# schemat-eagle.net
KiCad netlist of a schematic drawn in EAGLE
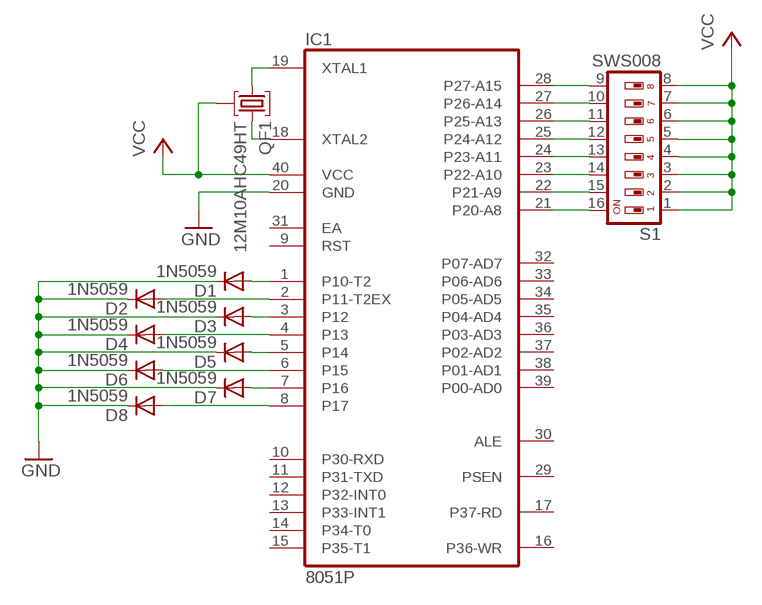
[diagram p0: schematic, sheet 1]

(export (version "E")
  (design (tool "Eeschema 10.0.6"))
  (components
    (comp (ref "D1")
      (value "1N5059")
      (footprint "eagle-import:DO204-10")
      (libsource (lib "eagle-import") (part "1N5059"))
    )
    (comp (ref "D2")
      (value "1N5059")
      (footprint "eagle-import:DO204-10")
      (libsource (lib "eagle-import") (part "1N5059"))
    )
    (comp (ref "D3")
      (value "1N5059")
      (footprint "eagle-import:DO204-10")
      (libsource (lib "eagle-import") (part "1N5059"))
    )
    (comp (ref "D4")
      (value "1N5059")
      (footprint "eagle-import:DO204-10")
      (libsource (lib "eagle-import") (part "1N5059"))
    )
    (comp (ref "D5")
      (value "1N5059")
      (footprint "eagle-import:DO204-10")
      (libsource (lib "eagle-import") (part "1N5059"))
    )
    (comp (ref "D6")
      (value "1N5059")
      (footprint "eagle-import:DO204-10")
      (libsource (lib "eagle-import") (part "1N5059"))
    )
    (comp (ref "D7")
      (value "1N5059")
      (footprint "eagle-import:DO204-10")
      (libsource (lib "eagle-import") (part "1N5059"))
    )
    (comp (ref "D8")
      (value "1N5059")
      (footprint "eagle-import:DO204-10")
      (libsource (lib "eagle-import") (part "1N5059"))
    )
    (comp (ref "IC1")
      (value "8051P")
      (footprint "eagle-import:DIL40")
      (libsource (lib "eagle-import") (part "8051P"))
    )
    (comp (ref "QF1")
      (value "12M10AHC49HT")
      (footprint "eagle-import:HC49U")
      (libsource (lib "eagle-import") (part "12M10AHC49HT"))
    )
    (comp (ref "S1")
      (value "SWS008")
      (footprint "eagle-import:SMS-008")
      (libsource (lib "eagle-import") (part "SWS008"))
    )
  )
  (nets
    (net (code "1") (name "GND") (class "Default")
      (node (ref "D1") (pin "C") (pinfunction "C_C") (pintype "passive"))
      (node (ref "D2") (pin "C") (pinfunction "C_C") (pintype "passive"))
      (node (ref "D3") (pin "C") (pinfunction "C_C") (pintype "passive"))
      (node (ref "D4") (pin "C") (pinfunction "C_C") (pintype "passive"))
      (node (ref "D5") (pin "C") (pinfunction "C_C") (pintype "passive"))
      (node (ref "D6") (pin "C") (pinfunction "C_C") (pintype "passive"))
      (node (ref "D7") (pin "C") (pinfunction "C_C") (pintype "passive"))
      (node (ref "D8") (pin "C") (pinfunction "C_C") (pintype "passive"))
      (node (ref "IC1") (pin "20") (pinfunction "GND_20") (pintype "power_in"))
    )
    (net (code "2") (name "Net-(IC1-P10-T2)") (class "Default")
      (node (ref "D1") (pin "A") (pinfunction "A_A") (pintype "passive"))
      (node (ref "IC1") (pin "1") (pinfunction "P10-T2_1") (pintype "bidirectional"))
    )
    (net (code "3") (name "Net-(IC1-P11-T2EX)") (class "Default")
      (node (ref "D2") (pin "A") (pinfunction "A_A") (pintype "passive"))
      (node (ref "IC1") (pin "2") (pinfunction "P11-T2EX_2") (pintype "bidirectional"))
    )
    (net (code "4") (name "Net-(IC1-P12)") (class "Default")
      (node (ref "D3") (pin "A") (pinfunction "A_A") (pintype "passive"))
      (node (ref "IC1") (pin "3") (pinfunction "P12_3") (pintype "bidirectional"))
    )
    (net (code "5") (name "Net-(IC1-P13)") (class "Default")
      (node (ref "D4") (pin "A") (pinfunction "A_A") (pintype "passive"))
      (node (ref "IC1") (pin "4") (pinfunction "P13_4") (pintype "bidirectional"))
    )
    (net (code "6") (name "Net-(IC1-P14)") (class "Default")
      (node (ref "D5") (pin "A") (pinfunction "A_A") (pintype "passive"))
      (node (ref "IC1") (pin "5") (pinfunction "P14_5") (pintype "bidirectional"))
    )
    (net (code "7") (name "Net-(IC1-P15)") (class "Default")
      (node (ref "D6") (pin "A") (pinfunction "A_A") (pintype "passive"))
      (node (ref "IC1") (pin "6") (pinfunction "P15_6") (pintype "bidirectional"))
    )
    (net (code "8") (name "Net-(IC1-P16)") (class "Default")
      (node (ref "D7") (pin "A") (pinfunction "A_A") (pintype "passive"))
      (node (ref "IC1") (pin "7") (pinfunction "P16_7") (pintype "bidirectional"))
    )
    (net (code "9") (name "Net-(IC1-P17)") (class "Default")
      (node (ref "D8") (pin "A") (pinfunction "A_A") (pintype "passive"))
      (node (ref "IC1") (pin "8") (pinfunction "P17_8") (pintype "bidirectional"))
    )
    (net (code "10") (name "Net-(IC1-P20-A8)") (class "Default")
      (node (ref "IC1") (pin "21") (pinfunction "P20-A8_21") (pintype "bidirectional"))
      (node (ref "S1") (pin "16") (pinfunction "16_16") (pintype "passive"))
    )
    (net (code "11") (name "Net-(IC1-P21-A9)") (class "Default")
      (node (ref "IC1") (pin "22") (pinfunction "P21-A9_22") (pintype "bidirectional"))
      (node (ref "S1") (pin "15") (pinfunction "15_15") (pintype "passive"))
    )
    (net (code "12") (name "Net-(IC1-P22-A10)") (class "Default")
      (node (ref "IC1") (pin "23") (pinfunction "P22-A10_23") (pintype "bidirectional"))
      (node (ref "S1") (pin "14") (pinfunction "14_14") (pintype "passive"))
    )
    (net (code "13") (name "Net-(IC1-P23-A11)") (class "Default")
      (node (ref "IC1") (pin "24") (pinfunction "P23-A11_24") (pintype "bidirectional"))
      (node (ref "S1") (pin "13") (pinfunction "13_13") (pintype "passive"))
    )
    (net (code "14") (name "Net-(IC1-P24-A12)") (class "Default")
      (node (ref "IC1") (pin "25") (pinfunction "P24-A12_25") (pintype "bidirectional"))
      (node (ref "S1") (pin "12") (pinfunction "12_12") (pintype "passive"))
    )
    (net (code "15") (name "Net-(IC1-P25-A13)") (class "Default")
      (node (ref "IC1") (pin "26") (pinfunction "P25-A13_26") (pintype "bidirectional"))
      (node (ref "S1") (pin "11") (pinfunction "11_11") (pintype "passive"))
    )
    (net (code "16") (name "Net-(IC1-P26-A14)") (class "Default")
      (node (ref "IC1") (pin "27") (pinfunction "P26-A14_27") (pintype "bidirectional"))
      (node (ref "S1") (pin "10") (pinfunction "10_10") (pintype "passive"))
    )
    (net (code "17") (name "Net-(IC1-P27-A15)") (class "Default")
      (node (ref "IC1") (pin "28") (pinfunction "P27-A15_28") (pintype "bidirectional"))
      (node (ref "S1") (pin "9") (pinfunction "9_9") (pintype "passive"))
    )
    (net (code "18") (name "Net-(IC1-XTAL1)") (class "Default")
      (node (ref "IC1") (pin "19") (pinfunction "XTAL1_19") (pintype "input"))
      (node (ref "QF1") (pin "1") (pinfunction "1_1") (pintype "passive"))
    )
    (net (code "19") (name "Net-(IC1-XTAL2)") (class "Default")
      (node (ref "IC1") (pin "18") (pinfunction "XTAL2_18") (pintype "input"))
      (node (ref "QF1") (pin "3") (pinfunction "3_3") (pintype "passive"))
    )
    (net (code "20") (name "VCC") (class "Default")
      (node (ref "IC1") (pin "40") (pinfunction "VCC_40") (pintype "power_in"))
      (node (ref "QF1") (pin "2") (pinfunction "2_2") (pintype "passive"))
      (node (ref "S1") (pin "1") (pinfunction "1_1") (pintype "passive"))
      (node (ref "S1") (pin "2") (pinfunction "2_2") (pintype "passive"))
      (node (ref "S1") (pin "3") (pinfunction "3_3") (pintype "passive"))
      (node (ref "S1") (pin "4") (pinfunction "4_4") (pintype "passive"))
      (node (ref "S1") (pin "5") (pinfunction "5_5") (pintype "passive"))
      (node (ref "S1") (pin "6") (pinfunction "6_6") (pintype "passive"))
      (node (ref "S1") (pin "7") (pinfunction "7_7") (pintype "passive"))
      (node (ref "S1") (pin "8") (pinfunction "8_8") (pintype "passive"))
    )
    (net (code "21") (name "unconnected-(IC1-ALE-Pad30)") (class "Default")
      (node (ref "IC1") (pin "30") (pinfunction "ALE_30") (pintype "output"))
    )
    (net (code "22") (name "unconnected-(IC1-EA-Pad31)") (class "Default")
      (node (ref "IC1") (pin "31") (pinfunction "EA_31") (pintype "input"))
    )
    (net (code "23") (name "unconnected-(IC1-P00-AD0-Pad39)") (class "Default")
      (node (ref "IC1") (pin "39") (pinfunction "P00-AD0_39") (pintype "bidirectional"))
    )
    (net (code "24") (name "unconnected-(IC1-P01-AD1-Pad38)") (class "Default")
      (node (ref "IC1") (pin "38") (pinfunction "P01-AD1_38") (pintype "bidirectional"))
    )
    (net (code "25") (name "unconnected-(IC1-P02-AD2-Pad37)") (class "Default")
      (node (ref "IC1") (pin "37") (pinfunction "P02-AD2_37") (pintype "bidirectional"))
    )
    (net (code "26") (name "unconnected-(IC1-P03-AD3-Pad36)") (class "Default")
      (node (ref "IC1") (pin "36") (pinfunction "P03-AD3_36") (pintype "bidirectional"))
    )
    (net (code "27") (name "unconnected-(IC1-P04-AD4-Pad35)") (class "Default")
      (node (ref "IC1") (pin "35") (pinfunction "P04-AD4_35") (pintype "bidirectional"))
    )
    (net (code "28") (name "unconnected-(IC1-P05-AD5-Pad34)") (class "Default")
      (node (ref "IC1") (pin "34") (pinfunction "P05-AD5_34") (pintype "bidirectional"))
    )
    (net (code "29") (name "unconnected-(IC1-P06-AD6-Pad33)") (class "Default")
      (node (ref "IC1") (pin "33") (pinfunction "P06-AD6_33") (pintype "bidirectional"))
    )
    (net (code "30") (name "unconnected-(IC1-P07-AD7-Pad32)") (class "Default")
      (node (ref "IC1") (pin "32") (pinfunction "P07-AD7_32") (pintype "bidirectional"))
    )
    (net (code "31") (name "unconnected-(IC1-P30-RXD-Pad10)") (class "Default")
      (node (ref "IC1") (pin "10") (pinfunction "P30-RXD_10") (pintype "bidirectional"))
    )
    (net (code "32") (name "unconnected-(IC1-P31-TXD-Pad11)") (class "Default")
      (node (ref "IC1") (pin "11") (pinfunction "P31-TXD_11") (pintype "bidirectional"))
    )
    (net (code "33") (name "unconnected-(IC1-P32-INT0-Pad12)") (class "Default")
      (node (ref "IC1") (pin "12") (pinfunction "P32-INT0_12") (pintype "bidirectional"))
    )
    (net (code "34") (name "unconnected-(IC1-P33-INT1-Pad13)") (class "Default")
      (node (ref "IC1") (pin "13") (pinfunction "P33-INT1_13") (pintype "bidirectional"))
    )
    (net (code "35") (name "unconnected-(IC1-P34-T0-Pad14)") (class "Default")
      (node (ref "IC1") (pin "14") (pinfunction "P34-T0_14") (pintype "bidirectional"))
    )
    (net (code "36") (name "unconnected-(IC1-P35-T1-Pad15)") (class "Default")
      (node (ref "IC1") (pin "15") (pinfunction "P35-T1_15") (pintype "bidirectional"))
    )
    (net (code "37") (name "unconnected-(IC1-P36-WR-Pad16)") (class "Default")
      (node (ref "IC1") (pin "16") (pinfunction "P36-WR_16") (pintype "bidirectional"))
    )
    (net (code "38") (name "unconnected-(IC1-P37-RD-Pad17)") (class "Default")
      (node (ref "IC1") (pin "17") (pinfunction "P37-RD_17") (pintype "bidirectional"))
    )
    (net (code "39") (name "unconnected-(IC1-PSEN-Pad29)") (class "Default")
      (node (ref "IC1") (pin "29") (pinfunction "PSEN_29") (pintype "output"))
    )
    (net (code "40") (name "unconnected-(IC1-RST-Pad9)") (class "Default")
      (node (ref "IC1") (pin "9") (pinfunction "RST_9") (pintype "input"))
    )
  )
)
